# GearDisplay.net
KiCad netlist of a schematic drawn in Altium Designer
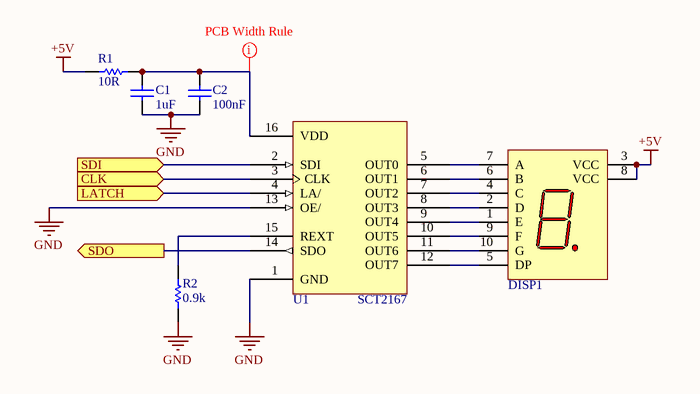
[diagram p0: GearDisplay.SchDoc]

(export (version "E")
  (design (tool "Eeschema 10.0.6"))
  (components
    (comp (ref "C1")
      (value "1uF")
      (footprint "CAP_0805_IPC_MD")
      (description "Capacitor")
      (fields (field (name "MANUFACTURER") "Samsung") (field (name "Comment") "Cap"))
      (libsource (lib "DataLogger") (part "Cap"))
    )
    (comp (ref "C2")
      (value "100nF")
      (footprint "CAP_0805_IPC_MD")
      (description "Capacitor")
      (fields (field (name "MANUFACTURER") "Samsung") (field (name "Comment") "Cap"))
      (libsource (lib "DataLogger") (part "Cap"))
    )
    (comp (ref "DISP1")
      (value "7SEG DISP")
      (footprint "7_SEG_LED_0.8_INCH")
      (description "OPTO PLUS LED CORP. OPD-S8023LB-BW")
      (fields (field (name "MANUFACTURER") "Opto Plus Led Corp."))
      (libsource (lib "Dashboard") (part "7SEG DISP"))
    )
    (comp (ref "R1")
      (value "10R")
      (footprint "RES_0805_IPC_MD")
      (description "Resistor")
      (fields (field (name "MANUFACTURER") "Royal Ohm") (field (name "Comment") "Res"))
      (libsource (lib "Dashboard") (part "Res"))
    )
    (comp (ref "R2")
      (value "0.9k")
      (footprint "RES_0805_IPC_MD")
      (description "Resistor")
      (fields (field (name "MANUFACTURER") "Royal Ohm") (field (name "Comment") "Res"))
      (libsource (lib "Dashboard") (part "Res"))
    )
    (comp (ref "U1")
      (value "SCT2167")
      (footprint "SSOP_16_IPC_MD")
      (description "Led controller")
      (fields (field (name "MANUFACTURER") "Starchips Technology"))
      (libsource (lib "Dashboard") (part "SCT2167"))
    )
  )
  (nets
    (net (code "1") (name "+5V") (class "Default")
      (node (ref "DISP1") (pin "3") (pinfunction "VCC_3") (pintype "power_in"))
      (node (ref "DISP1") (pin "8") (pinfunction "VCC_8") (pintype "power_in"))
      (node (ref "R1") (pin "1") (pinfunction "1_1") (pintype "passive"))
    )
    (net (code "2") (name "/CLK") (class "Default")
      (node (ref "U1") (pin "3") (pinfunction "CLK_3") (pintype "passive"))
    )
    (net (code "3") (name "/LATCH") (class "Default")
      (node (ref "U1") (pin "4") (pinfunction "LA/_4") (pintype "input"))
    )
    (net (code "4") (name "/SDI") (class "Default")
      (node (ref "U1") (pin "2") (pinfunction "SDI_2") (pintype "input"))
    )
    (net (code "5") (name "/SDO") (class "Default")
      (node (ref "U1") (pin "14") (pinfunction "SDO_14") (pintype "output"))
    )
    (net (code "6") (name "GND") (class "Default")
      (node (ref "C1") (pin "1") (pinfunction "1_1") (pintype "passive"))
      (node (ref "C2") (pin "1") (pinfunction "1_1") (pintype "passive"))
      (node (ref "R2") (pin "2") (pinfunction "2_2") (pintype "passive"))
      (node (ref "U1") (pin "1") (pinfunction "GND_1") (pintype "power_in"))
      (node (ref "U1") (pin "13") (pinfunction "OE/_13") (pintype "input"))
    )
    (net (code "7") (name "Net-(DISP1-A)") (class "Default")
      (node (ref "DISP1") (pin "7") (pinfunction "A_7") (pintype "passive"))
      (node (ref "U1") (pin "5") (pinfunction "OUT0_5") (pintype "open_collector"))
    )
    (net (code "8") (name "Net-(DISP1-B)") (class "Default")
      (node (ref "DISP1") (pin "6") (pinfunction "B_6") (pintype "passive"))
      (node (ref "U1") (pin "6") (pinfunction "OUT1_6") (pintype "open_collector"))
    )
    (net (code "9") (name "Net-(DISP1-C)") (class "Default")
      (node (ref "DISP1") (pin "4") (pinfunction "C_4") (pintype "passive"))
      (node (ref "U1") (pin "7") (pinfunction "OUT2_7") (pintype "open_collector"))
    )
    (net (code "10") (name "Net-(DISP1-D)") (class "Default")
      (node (ref "DISP1") (pin "2") (pinfunction "D_2") (pintype "passive"))
      (node (ref "U1") (pin "8") (pinfunction "OUT3_8") (pintype "open_collector"))
    )
    (net (code "11") (name "Net-(DISP1-DP)") (class "Default")
      (node (ref "DISP1") (pin "5") (pinfunction "DP_5") (pintype "passive"))
      (node (ref "U1") (pin "12") (pinfunction "OUT7_12") (pintype "open_collector"))
    )
    (net (code "12") (name "Net-(DISP1-E)") (class "Default")
      (node (ref "DISP1") (pin "1") (pinfunction "E_1") (pintype "passive"))
      (node (ref "U1") (pin "9") (pinfunction "OUT4_9") (pintype "open_collector"))
    )
    (net (code "13") (name "Net-(DISP1-F)") (class "Default")
      (node (ref "DISP1") (pin "9") (pinfunction "F_9") (pintype "passive"))
      (node (ref "U1") (pin "10") (pinfunction "OUT5_10") (pintype "open_collector"))
    )
    (net (code "14") (name "Net-(DISP1-G)") (class "Default")
      (node (ref "DISP1") (pin "10") (pinfunction "G_10") (pintype "passive"))
      (node (ref "U1") (pin "11") (pinfunction "OUT6_11") (pintype "open_collector"))
    )
    (net (code "15") (name "Net-(U1-REXT)") (class "Default")
      (node (ref "R2") (pin "1") (pinfunction "1_1") (pintype "passive"))
      (node (ref "U1") (pin "15") (pinfunction "REXT_15") (pintype "passive"))
    )
    (net (code "16") (name "Net-(U1-VDD)") (class "Default")
      (node (ref "C1") (pin "2") (pinfunction "2_2") (pintype "passive"))
      (node (ref "C2") (pin "2") (pinfunction "2_2") (pintype "passive"))
      (node (ref "R1") (pin "2") (pinfunction "2_2") (pintype "passive"))
      (node (ref "U1") (pin "16") (pinfunction "VDD_16") (pintype "power_in"))
    )
  )
)
